# DataAcquisitonBoard.net
KiCad netlist of a schematic drawn in Altium Designer
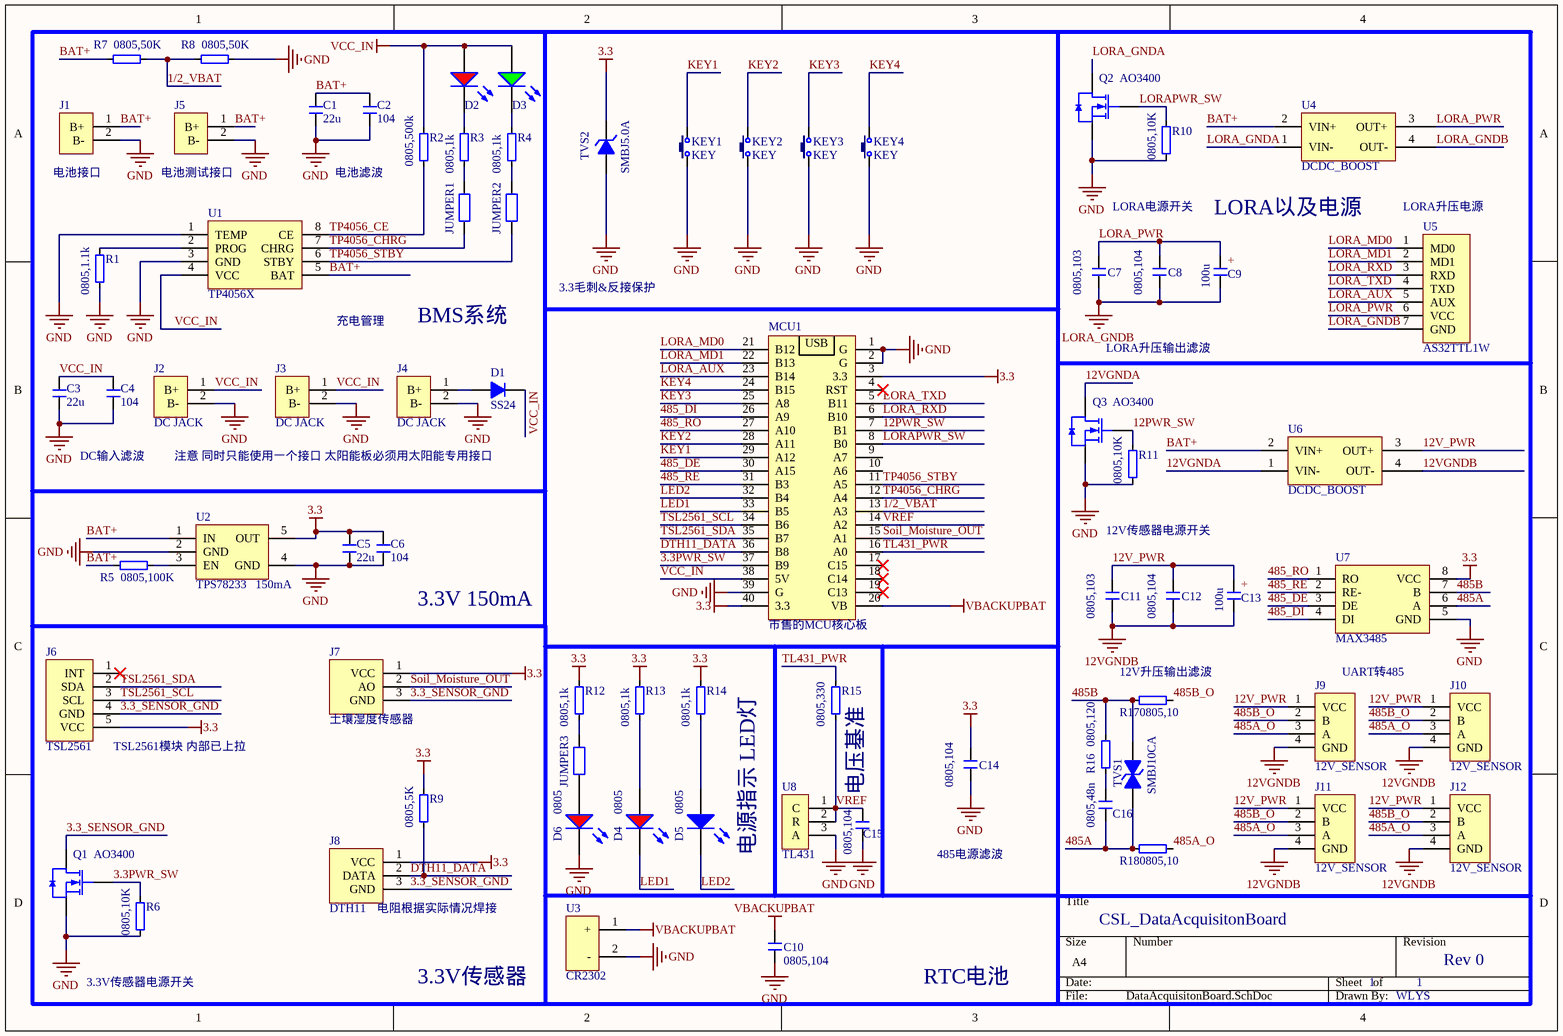
[diagram p0: DataAcquisitonBoard.SchDoc]

(export (version "E")
  (design (tool "Eeschema 10.0.6"))
  (components
    (comp (ref "C1")
      (value "22u")
      (footprint "0805_C")
      (libsource (lib "DataAcquisitonBoard") (part "C0805"))
    )
    (comp (ref "C2")
      (value "104")
      (footprint "0805_C")
      (libsource (lib "DataAcquisitonBoard") (part "C0805"))
    )
    (comp (ref "C3")
      (value "22u")
      (footprint "0805_C")
      (libsource (lib "DataAcquisitonBoard") (part "C0805"))
    )
    (comp (ref "C4")
      (value "104")
      (footprint "0805_C")
      (libsource (lib "DataAcquisitonBoard") (part "C0805"))
    )
    (comp (ref "C5")
      (value "22u")
      (footprint "0805_C")
      (libsource (lib "DataAcquisitonBoard") (part "C0805"))
    )
    (comp (ref "C6")
      (value "104")
      (footprint "0805_C")
      (libsource (lib "DataAcquisitonBoard") (part "C0805"))
    )
    (comp (ref "C7")
      (value "0805,103")
      (footprint "0805_C")
      (libsource (lib "DataAcquisitonBoard") (part "C0805"))
    )
    (comp (ref "C8")
      (value "0805,104")
      (footprint "0805_C")
      (libsource (lib "DataAcquisitonBoard") (part "C0805"))
    )
    (comp (ref "C9")
      (value "100u")
      (footprint "CAP 2.5*6.3*11.2")
      (libsource (lib "DataAcquisitonBoard") (part "C直插电解"))
    )
    (comp (ref "C10")
      (value "0805,104")
      (footprint "0805_C")
      (libsource (lib "DataAcquisitonBoard") (part "C0805"))
    )
    (comp (ref "C11")
      (value "0805,103")
      (footprint "0805_C")
      (libsource (lib "DataAcquisitonBoard") (part "C0805"))
    )
    (comp (ref "C12")
      (value "0805,104")
      (footprint "0805_C")
      (libsource (lib "DataAcquisitonBoard") (part "C0805"))
    )
    (comp (ref "C13")
      (value "100u")
      (footprint "CAP 2.5*6.3*11.2")
      (libsource (lib "DataAcquisitonBoard") (part "C直插电解"))
    )
    (comp (ref "C14")
      (value "0805,104")
      (footprint "0805_C")
      (libsource (lib "DataAcquisitonBoard") (part "C0805"))
    )
    (comp (ref "C15")
      (value "0805,104")
      (footprint "0805_C")
      (libsource (lib "DataAcquisitonBoard") (part "C0805"))
    )
    (comp (ref "C16")
      (value "0805,48n")
      (footprint "0805_C")
      (libsource (lib "DataAcquisitonBoard") (part "C0805"))
    )
    (comp (ref "D1")
      (value "SS24")
      (footprint "SMB(DO-214AA)_S1")
      (description "Diodo diode")
      (libsource (lib "DataAcquisitonBoard") (part "Diodo_214AA"))
    )
    (comp (ref "D2")
      (value "~")
      (footprint "0805_LED_S1")
      (description "发光二极管")
      (libsource (lib "DataAcquisitonBoard") (part "0805 红灯"))
    )
    (comp (ref "D3")
      (value "~")
      (footprint "0805_LED_S1")
      (description "发光二极管")
      (libsource (lib "DataAcquisitonBoard") (part "0805 翠绿"))
    )
    (comp (ref "D4")
      (value "0805")
      (footprint "0805_LED_S1")
      (description "发光二极管")
      (libsource (lib "DataAcquisitonBoard") (part "0805 红灯"))
    )
    (comp (ref "D5")
      (value "0805")
      (footprint "0805_LED_S1")
      (description "发光二极管")
      (libsource (lib "DataAcquisitonBoard") (part "0805 蓝灯"))
    )
    (comp (ref "D6")
      (value "0805")
      (footprint "0805_LED_S1")
      (description "发光二极管")
      (libsource (lib "DataAcquisitonBoard") (part "0805 红灯"))
    )
    (comp (ref "J1")
      (value "电池接口")
      (footprint "XH2.54-LI-2P")
      (libsource (lib "DataAcquisitonBoard") (part "BAT"))
    )
    (comp (ref "J2")
      (value "DC JACK")
      (footprint "XH2.54-LI-2P")
      (description "DC充电输入接口")
      (libsource (lib "DataAcquisitonBoard") (part "DCINPUT"))
    )
    (comp (ref "J3")
      (value "DC JACK")
      (footprint "XH2.54-LI-2P")
      (description "DC充电输入接口")
      (libsource (lib "DataAcquisitonBoard") (part "DCINPUT"))
    )
    (comp (ref "J4")
      (value "DC JACK")
      (footprint "XH2.54-LI-2P")
      (description "DC充电输入接口")
      (libsource (lib "DataAcquisitonBoard") (part "DCINPUT"))
    )
    (comp (ref "J5")
      (value "电池测试接口")
      (footprint "XH2.54-LI-2P")
      (description "电池接口")
      (libsource (lib "DataAcquisitonBoard") (part "BAT"))
    )
    (comp (ref "J6")
      (value "TSL2561")
      (footprint "XH2.54-LI-5P")
      (description "IIC总线光强传感器模块 已经集成IIC上拉电阻")
      (libsource (lib "DataAcquisitonBoard") (part "TSL2561"))
    )
    (comp (ref "J7")
      (value "土壤湿度传感器")
      (footprint "XH2.54-LI-3P")
      (libsource (lib "DataAcquisitonBoard") (part "土壤湿度"))
    )
    (comp (ref "J8")
      (value "DTH11")
      (footprint "XH2.54-LI-3P")
      (description "数字式温湿度传感器")
      (libsource (lib "DataAcquisitonBoard") (part "DTH11"))
    )
    (comp (ref "J9")
      (value "12V_SENSOR")
      (footprint "XH2.54-LI-4P")
      (description "12V传感器接口 包括 12V GND 485")
      (libsource (lib "DataAcquisitonBoard") (part "12V_SENSOR"))
    )
    (comp (ref "J10")
      (value "12V_SENSOR")
      (footprint "XH2.54-LI-4P")
      (description "12V传感器接口 包括 12V GND 485")
      (libsource (lib "DataAcquisitonBoard") (part "12V_SENSOR"))
    )
    (comp (ref "J11")
      (value "12V_SENSOR")
      (footprint "XH2.54-LI-4P")
      (description "12V传感器接口 包括 12V GND 485")
      (libsource (lib "DataAcquisitonBoard") (part "12V_SENSOR"))
    )
    (comp (ref "J12")
      (value "12V_SENSOR")
      (footprint "XH2.54-LI-4P")
      (description "12V传感器接口 包括 12V GND 485")
      (libsource (lib "DataAcquisitonBoard") (part "12V_SENSOR"))
    )
    (comp (ref "JUMPER1")
      (value "0805_JUMPER")
      (footprint "JUMPER")
      (description "0805大小的跳线")
      (libsource (lib "DataAcquisitonBoard") (part "0805_JUMPER"))
    )
    (comp (ref "JUMPER2")
      (value "0805_JUMPER")
      (footprint "JUMPER")
      (description "0805大小的跳线")
      (libsource (lib "DataAcquisitonBoard") (part "0805_JUMPER"))
    )
    (comp (ref "JUMPER3")
      (value "0805_JUMPER")
      (footprint "JUMPER")
      (description "0805大小的跳线")
      (libsource (lib "DataAcquisitonBoard") (part "0805_JUMPER"))
    )
    (comp (ref "KEY1")
      (value "KEY")
      (footprint "TSW SMD-4*4*1.5")
      (description "Tact Switch")
      (libsource (lib "DataAcquisitonBoard") (part "TSW_4x4-SMT"))
    )
    (comp (ref "KEY2")
      (value "KEY")
      (footprint "TSW SMD-4*4*1.5")
      (description "Tact Switch")
      (libsource (lib "DataAcquisitonBoard") (part "TSW_4x4-SMT"))
    )
    (comp (ref "KEY3")
      (value "KEY")
      (footprint "TSW SMD-4*4*1.5")
      (description "Tact Switch")
      (libsource (lib "DataAcquisitonBoard") (part "TSW_4x4-SMT"))
    )
    (comp (ref "KEY4")
      (value "KEY")
      (footprint "TSW SMD-4*4*1.5")
      (description "Tact Switch")
      (libsource (lib "DataAcquisitonBoard") (part "TSW_4x4-SMT"))
    )
    (comp (ref "MCU1")
      (value "市售的MCU核心板")
      (footprint "STM32F103C8T6_CORE")
      (libsource (lib "DataAcquisitonBoard") (part "STM32F103C8T6_CORE"))
    )
    (comp (ref "Q1")
      (value "AO3400")
      (footprint "SOT-23(SOT-23-3)")
      (description "MOS(场效应管)")
      (libsource (lib "DataAcquisitonBoard") (part "AO3400A N道沟 X0YV1T SOT-23"))
    )
    (comp (ref "Q2")
      (value "AO3400")
      (footprint "SOT-23(SOT-23-3)")
      (description "MOS(场效应管)")
      (libsource (lib "DataAcquisitonBoard") (part "AO3400A N道沟 X0YV1T SOT-23"))
    )
    (comp (ref "Q3")
      (value "AO3400")
      (footprint "SOT-23(SOT-23-3)")
      (description "MOS(场效应管)")
      (libsource (lib "DataAcquisitonBoard") (part "AO3400A N道沟 X0YV1T SOT-23"))
    )
    (comp (ref "R1")
      (value "0805,1.1k")
      (footprint "0805_R")
      (libsource (lib "DataAcquisitonBoard") (part "R0805"))
    )
    (comp (ref "R2")
      (value "0805,500k")
      (footprint "0805_R")
      (libsource (lib "DataAcquisitonBoard") (part "R0805"))
    )
    (comp (ref "R3")
      (value "0805,1k")
      (footprint "0805_R")
      (libsource (lib "DataAcquisitonBoard") (part "R0805"))
    )
    (comp (ref "R4")
      (value "0805,1k")
      (footprint "0805_R")
      (libsource (lib "DataAcquisitonBoard") (part "R0805"))
    )
    (comp (ref "R5")
      (value "0805,100K")
      (footprint "0805_R")
      (libsource (lib "DataAcquisitonBoard") (part "R0805"))
    )
    (comp (ref "R6")
      (value "0805,10K")
      (footprint "0805_R")
      (libsource (lib "DataAcquisitonBoard") (part "R0805"))
    )
    (comp (ref "R7")
      (value "0805,50K")
      (footprint "0805_R")
      (libsource (lib "DataAcquisitonBoard") (part "R0805"))
    )
    (comp (ref "R8")
      (value "0805,50K")
      (footprint "0805_R")
      (libsource (lib "DataAcquisitonBoard") (part "R0805"))
    )
    (comp (ref "R9")
      (value "0805,5K")
      (footprint "0805_R")
      (libsource (lib "DataAcquisitonBoard") (part "R0805"))
    )
    (comp (ref "R10")
      (value "0805,10K")
      (footprint "0805_R")
      (libsource (lib "DataAcquisitonBoard") (part "R0805"))
    )
    (comp (ref "R11")
      (value "0805,10K")
      (footprint "0805_R")
      (libsource (lib "DataAcquisitonBoard") (part "R0805"))
    )
    (comp (ref "R12")
      (value "0805,1k")
      (footprint "0805_R")
      (libsource (lib "DataAcquisitonBoard") (part "R0805"))
    )
    (comp (ref "R13")
      (value "0805,1k")
      (footprint "0805_R")
      (libsource (lib "DataAcquisitonBoard") (part "R0805"))
    )
    (comp (ref "R14")
      (value "0805,1k")
      (footprint "0805_R")
      (libsource (lib "DataAcquisitonBoard") (part "R0805"))
    )
    (comp (ref "R15")
      (value "0805,330")
      (footprint "0805_R")
      (libsource (lib "DataAcquisitonBoard") (part "R0805"))
    )
    (comp (ref "R16")
      (value "0805,120")
      (footprint "0805_R")
      (libsource (lib "DataAcquisitonBoard") (part "R0805"))
    )
    (comp (ref "R17")
      (value "0805,10")
      (footprint "0805_R")
      (libsource (lib "DataAcquisitonBoard") (part "R0805"))
    )
    (comp (ref "R18")
      (value "0805,10")
      (footprint "0805_R")
      (libsource (lib "DataAcquisitonBoard") (part "R0805"))
    )
    (comp (ref "TVS1")
      (value "SMBJ10CA")
      (footprint "SMB(DO-214AA)_S1")
      (description "双向TVS 214AA封装")
      (libsource (lib "DataAcquisitonBoard") (part "TVS_214AA_BI"))
    )
    (comp (ref "TVS2")
      (value "SMBJ5.0A")
      (footprint "SMB(DO-214AA)_S1")
      (description "TVS diode")
      (libsource (lib "DataAcquisitonBoard") (part "TVS_214AA"))
    )
    (comp (ref "U1")
      (value "TP4056X")
      (footprint "SOIC-8_150mil")
      (description "防反接锂电池充电管理IC")
      (libsource (lib "DataAcquisitonBoard") (part "TP4056X"))
    )
    (comp (ref "U2")
      (value "TPS78233")
      (footprint "SOT-23-5")
      (description "Regulator_SMT")
      (fields (field (name "版权归属") "源创客"))
      (libsource (lib "DataAcquisitonBoard") (part "TPS782"))
    )
    (comp (ref "U3")
      (value "CR2302")
      (footprint "CR2032_A")
      (description "CR2302 3V电池")
      (libsource (lib "DataAcquisitonBoard") (part "CR2302"))
    )
    (comp (ref "U4")
      (value "DCDC_BOOST")
      (footprint "BOOSTER")
      (libsource (lib "DataAcquisitonBoard") (part "DCDC_BOOST"))
    )
    (comp (ref "U5")
      (value "AS32TTL1W")
      (footprint "LORA")
      (description "1W LORA无线串口")
      (libsource (lib "DataAcquisitonBoard") (part "LORA_AS32TTL1W"))
    )
    (comp (ref "U6")
      (value "DCDC_BOOST")
      (footprint "BOOSTER")
      (libsource (lib "DataAcquisitonBoard") (part "DCDC_BOOST"))
    )
    (comp (ref "U7")
      (value "MAX3485")
      (footprint "SOIC-8_150mil")
      (description "3.3V供电带关断485半双工收发器")
      (libsource (lib "DataAcquisitonBoard") (part "MAX3485"))
    )
    (comp (ref "U8")
      (value "TL431")
      (footprint "SOT-23(SOT-23-3)")
      (description "德州仪器TL431 非国产TL431")
      (libsource (lib "DataAcquisitonBoard") (part "TL431AIDBZR"))
    )
  )
  (nets
    (net (code "1") (name "/1{slash}2_VBAT") (class "Default")
      (node (ref "MCU1") (pin "13") (pinfunction "A3_13") (pintype "passive"))
      (node (ref "R7") (pin "1") (pinfunction "1_1") (pintype "passive"))
      (node (ref "R8") (pin "2") (pinfunction "2_2") (pintype "passive"))
    )
    (net (code "2") (name "/3.3PWR_SW") (class "Default")
      (node (ref "MCU1") (pin "37") (pinfunction "B9_37") (pintype "passive"))
      (node (ref "Q1") (pin "1") (pinfunction "G_1") (pintype "passive"))
      (node (ref "R6") (pin "1") (pinfunction "1_1") (pintype "passive"))
    )
    (net (code "3") (name "/3.3_SENSOR_GND") (class "Default")
      (node (ref "J6") (pin "4") (pinfunction "GND_4") (pintype "passive"))
      (node (ref "J7") (pin "3") (pinfunction "GND_3") (pintype "passive"))
      (node (ref "J8") (pin "3") (pinfunction "GND_3") (pintype "passive"))
      (node (ref "Q1") (pin "3") (pinfunction "D_3") (pintype "passive"))
    )
    (net (code "4") (name "/12PWR_SW") (class "Default")
      (node (ref "MCU1") (pin "7") (pinfunction "B1_7") (pintype "passive"))
      (node (ref "Q3") (pin "1") (pinfunction "G_1") (pintype "passive"))
      (node (ref "R11") (pin "1") (pinfunction "1_1") (pintype "passive"))
    )
    (net (code "5") (name "/12VGNDA") (class "Default")
      (node (ref "Q3") (pin "3") (pinfunction "D_3") (pintype "passive"))
      (node (ref "U6") (pin "1") (pinfunction "VIN-_1") (pintype "passive"))
    )
    (net (code "6") (name "/12V_PWR") (class "Default")
      (node (ref "C11") (pin "1") (pinfunction "1_1") (pintype "passive"))
      (node (ref "C12") (pin "1") (pinfunction "1_1") (pintype "passive"))
      (node (ref "C13") (pin "1") (pinfunction "1_1") (pintype "passive"))
      (node (ref "J10") (pin "1") (pinfunction "VCC_1") (pintype "passive"))
      (node (ref "J11") (pin "1") (pinfunction "VCC_1") (pintype "passive"))
      (node (ref "J12") (pin "1") (pinfunction "VCC_1") (pintype "passive"))
      (node (ref "J9") (pin "1") (pinfunction "VCC_1") (pintype "passive"))
      (node (ref "U6") (pin "3") (pinfunction "OUT+_3") (pintype "passive"))
    )
    (net (code "7") (name "/485A") (class "Default")
      (node (ref "C16") (pin "2") (pinfunction "2_2") (pintype "passive"))
      (node (ref "R18") (pin "2") (pinfunction "2_2") (pintype "passive"))
      (node (ref "TVS1") (pin "1") (pinfunction "A_1") (pintype "passive"))
      (node (ref "U7") (pin "6") (pinfunction "A_6") (pintype "passive"))
    )
    (net (code "8") (name "/485A_O") (class "Default")
      (node (ref "J10") (pin "3") (pinfunction "A_3") (pintype "passive"))
      (node (ref "J11") (pin "3") (pinfunction "A_3") (pintype "passive"))
      (node (ref "J12") (pin "3") (pinfunction "A_3") (pintype "passive"))
      (node (ref "J9") (pin "3") (pinfunction "A_3") (pintype "passive"))
      (node (ref "R18") (pin "1") (pinfunction "1_1") (pintype "passive"))
    )
    (net (code "9") (name "/485B") (class "Default")
      (node (ref "R16") (pin "1") (pinfunction "1_1") (pintype "passive"))
      (node (ref "R17") (pin "2") (pinfunction "2_2") (pintype "passive"))
      (node (ref "TVS1") (pin "2") (pinfunction "K_2") (pintype "passive"))
      (node (ref "U7") (pin "7") (pinfunction "B_7") (pintype "passive"))
    )
    (net (code "10") (name "/485B_O") (class "Default")
      (node (ref "J10") (pin "2") (pinfunction "B_2") (pintype "passive"))
      (node (ref "J11") (pin "2") (pinfunction "B_2") (pintype "passive"))
      (node (ref "J12") (pin "2") (pinfunction "B_2") (pintype "passive"))
      (node (ref "J9") (pin "2") (pinfunction "B_2") (pintype "passive"))
      (node (ref "R17") (pin "1") (pinfunction "1_1") (pintype "passive"))
    )
    (net (code "11") (name "/485_DE") (class "Default")
      (node (ref "MCU1") (pin "30") (pinfunction "A15_30") (pintype "passive"))
      (node (ref "U7") (pin "3") (pinfunction "DE_3") (pintype "passive"))
    )
    (net (code "12") (name "/485_DI") (class "Default")
      (node (ref "MCU1") (pin "26") (pinfunction "A9_26") (pintype "passive"))
      (node (ref "U7") (pin "4") (pinfunction "DI_4") (pintype "passive"))
    )
    (net (code "13") (name "/485_RE") (class "Default")
      (node (ref "MCU1") (pin "31") (pinfunction "B3_31") (pintype "passive"))
      (node (ref "U7") (pin "2") (pinfunction "RE-_2") (pintype "passive"))
    )
    (net (code "14") (name "/485_RO") (class "Default")
      (node (ref "MCU1") (pin "27") (pinfunction "A10_27") (pintype "passive"))
      (node (ref "U7") (pin "1") (pinfunction "RO_1") (pintype "passive"))
    )
    (net (code "15") (name "/BAT+") (class "Default")
      (node (ref "C1") (pin "1") (pinfunction "1_1") (pintype "passive"))
      (node (ref "C2") (pin "1") (pinfunction "1_1") (pintype "passive"))
      (node (ref "J1") (pin "1") (pinfunction "B+_1") (pintype "passive"))
      (node (ref "J5") (pin "1") (pinfunction "B+_1") (pintype "passive"))
      (node (ref "R5") (pin "2") (pinfunction "2_2") (pintype "passive"))
      (node (ref "R7") (pin "2") (pinfunction "2_2") (pintype "passive"))
      (node (ref "U1") (pin "5") (pinfunction "BAT_5") (pintype "passive"))
      (node (ref "U2") (pin "1") (pinfunction "IN_1") (pintype "passive"))
      (node (ref "U4") (pin "2") (pinfunction "VIN+_2") (pintype "passive"))
      (node (ref "U6") (pin "2") (pinfunction "VIN+_2") (pintype "passive"))
    )
    (net (code "16") (name "/DTH11_DATA") (class "Default")
      (node (ref "J8") (pin "2") (pinfunction "DATA_2") (pintype "passive"))
      (node (ref "MCU1") (pin "36") (pinfunction "B8_36") (pintype "passive"))
      (node (ref "R9") (pin "2") (pinfunction "2_2") (pintype "passive"))
    )
    (net (code "17") (name "/KEY1") (class "Default")
      (node (ref "KEY1") (pin "2") (pinfunction "2_2") (pintype "passive"))
      (node (ref "MCU1") (pin "29") (pinfunction "A12_29") (pintype "passive"))
    )
    (net (code "18") (name "/KEY2") (class "Default")
      (node (ref "KEY2") (pin "2") (pinfunction "2_2") (pintype "passive"))
      (node (ref "MCU1") (pin "28") (pinfunction "A11_28") (pintype "passive"))
    )
    (net (code "19") (name "/KEY3") (class "Default")
      (node (ref "KEY3") (pin "2") (pinfunction "2_2") (pintype "passive"))
      (node (ref "MCU1") (pin "25") (pinfunction "A8_25") (pintype "passive"))
    )
    (net (code "20") (name "/KEY4") (class "Default")
      (node (ref "KEY4") (pin "2") (pinfunction "2_2") (pintype "passive"))
      (node (ref "MCU1") (pin "24") (pinfunction "B15_24") (pintype "passive"))
    )
    (net (code "21") (name "/LED1") (class "Default")
      (node (ref "D4") (pin "K") (pinfunction "K_K") (pintype "passive"))
      (node (ref "MCU1") (pin "33") (pinfunction "B5_33") (pintype "passive"))
    )
    (net (code "22") (name "/LED2") (class "Default")
      (node (ref "D5") (pin "K") (pinfunction "K_K") (pintype "passive"))
      (node (ref "MCU1") (pin "32") (pinfunction "B4_32") (pintype "passive"))
    )
    (net (code "23") (name "/LORAPWR_SW") (class "Default")
      (node (ref "MCU1") (pin "8") (pinfunction "B0_8") (pintype "passive"))
      (node (ref "Q2") (pin "1") (pinfunction "G_1") (pintype "passive"))
      (node (ref "R10") (pin "1") (pinfunction "1_1") (pintype "passive"))
    )
    (net (code "24") (name "/LORA_AUX") (class "Default")
      (node (ref "MCU1") (pin "23") (pinfunction "B14_23") (pintype "passive"))
      (node (ref "U5") (pin "5") (pinfunction "AUX_5") (pintype "passive"))
    )
    (net (code "25") (name "/LORA_GNDA") (class "Default")
      (node (ref "Q2") (pin "3") (pinfunction "D_3") (pintype "passive"))
      (node (ref "U4") (pin "1") (pinfunction "VIN-_1") (pintype "passive"))
    )
    (net (code "26") (name "/LORA_MD0") (class "Default")
      (node (ref "MCU1") (pin "21") (pinfunction "B12_21") (pintype "passive"))
      (node (ref "U5") (pin "1") (pinfunction "MD0_1") (pintype "passive"))
    )
    (net (code "27") (name "/LORA_MD1") (class "Default")
      (node (ref "MCU1") (pin "22") (pinfunction "B13_22") (pintype "passive"))
      (node (ref "U5") (pin "2") (pinfunction "MD1_2") (pintype "passive"))
    )
    (net (code "28") (name "/LORA_PWR") (class "Default")
      (node (ref "C7") (pin "1") (pinfunction "1_1") (pintype "passive"))
      (node (ref "C8") (pin "1") (pinfunction "1_1") (pintype "passive"))
      (node (ref "C9") (pin "1") (pinfunction "1_1") (pintype "passive"))
      (node (ref "U4") (pin "3") (pinfunction "OUT+_3") (pintype "passive"))
      (node (ref "U5") (pin "6") (pinfunction "VCC_6") (pintype "passive"))
    )
    (net (code "29") (name "/LORA_RXD") (class "Default")
      (node (ref "MCU1") (pin "6") (pinfunction "B10_6") (pintype "passive"))
      (node (ref "U5") (pin "3") (pinfunction "RXD_3") (pintype "passive"))
    )
    (net (code "30") (name "/LORA_TXD") (class "Default")
      (node (ref "MCU1") (pin "5") (pinfunction "B11_5") (pintype "passive"))
      (node (ref "U5") (pin "4") (pinfunction "TXD_4") (pintype "passive"))
    )
    (net (code "31") (name "/Soil_Moisture_OUT") (class "Default")
      (node (ref "J7") (pin "2") (pinfunction "AO_2") (pintype "passive"))
      (node (ref "MCU1") (pin "15") (pinfunction "A1_15") (pintype "passive"))
    )
    (net (code "32") (name "/TL431_PWR") (class "Default")
      (node (ref "MCU1") (pin "16") (pinfunction "A0_16") (pintype "passive"))
      (node (ref "R15") (pin "2") (pinfunction "2_2") (pintype "passive"))
    )
    (net (code "33") (name "/TP4056_CE") (class "Default")
      (node (ref "R2") (pin "1") (pinfunction "1_1") (pintype "passive"))
      (node (ref "U1") (pin "8") (pinfunction "CE_8") (pintype "passive"))
    )
    (net (code "34") (name "/TP4056_CHRG") (class "Default")
      (node (ref "JUMPER1") (pin "1") (pinfunction "1_1") (pintype "passive"))
      (node (ref "MCU1") (pin "12") (pinfunction "A4_12") (pintype "passive"))
      (node (ref "U1") (pin "7") (pinfunction "CHRG_7") (pintype "passive"))
    )
    (net (code "35") (name "/TP4056_STBY") (class "Default")
      (node (ref "JUMPER2") (pin "1") (pinfunction "1_1") (pintype "passive"))
      (node (ref "MCU1") (pin "11") (pinfunction "A5_11") (pintype "passive"))
      (node (ref "U1") (pin "6") (pinfunction "STBY_6") (pintype "passive"))
    )
    (net (code "36") (name "/TSL2561_SCL") (class "Default")
      (node (ref "J6") (pin "3") (pinfunction "SCL_3") (pintype "passive"))
      (node (ref "MCU1") (pin "34") (pinfunction "B6_34") (pintype "passive"))
    )
    (net (code "37") (name "/TSL2561_SDA") (class "Default")
      (node (ref "J6") (pin "2") (pinfunction "SDA_2") (pintype "passive"))
      (node (ref "MCU1") (pin "35") (pinfunction "B7_35") (pintype "passive"))
    )
    (net (code "38") (name "/VREF") (class "Default")
      (node (ref "C15") (pin "1") (pinfunction "1_1") (pintype "passive"))
      (node (ref "MCU1") (pin "14") (pinfunction "A2_14") (pintype "passive"))
      (node (ref "R15") (pin "1") (pinfunction "1_1") (pintype "passive"))
      (node (ref "U8") (pin "1") (pinfunction "C_1") (pintype "passive"))
      (node (ref "U8") (pin "2") (pinfunction "R_2") (pintype "passive"))
    )
    (net (code "39") (name "3.3") (class "Default")
      (node (ref "C14") (pin "1") (pinfunction "1_1") (pintype "passive"))
      (node (ref "C5") (pin "1") (pinfunction "1_1") (pintype "passive"))
      (node (ref "C6") (pin "1") (pinfunction "1_1") (pintype "passive"))
      (node (ref "J6") (pin "5") (pinfunction "VCC_5") (pintype "passive"))
      (node (ref "J7") (pin "1") (pinfunction "VCC_1") (pintype "passive"))
      (node (ref "J8") (pin "1") (pinfunction "VCC_1") (pintype "passive"))
      (node (ref "MCU1") (pin "3") (pinfunction "3.3_3") (pintype "passive"))
      (node (ref "MCU1") (pin "40") (pinfunction "3.3_40") (pintype "passive"))
      (node (ref "R12") (pin "2") (pinfunction "2_2") (pintype "passive"))
      (node (ref "R13") (pin "2") (pinfunction "2_2") (pintype "passive"))
      (node (ref "R14") (pin "2") (pinfunction "2_2") (pintype "passive"))
      (node (ref "R9") (pin "1") (pinfunction "1_1") (pintype "passive"))
      (node (ref "TVS2") (pin "2") (pinfunction "K_2") (pintype "passive"))
      (node (ref "U2") (pin "5") (pinfunction "OUT_5") (pintype "passive"))
      (node (ref "U7") (pin "8") (pinfunction "VCC_8") (pintype "passive"))
    )
    (net (code "40") (name "12VGNDB") (class "Default")
      (node (ref "C11") (pin "2") (pinfunction "2_2") (pintype "passive"))
      (node (ref "C12") (pin "2") (pinfunction "2_2") (pintype "passive"))
      (node (ref "C13") (pin "2") (pinfunction "2_2") (pintype "passive"))
      (node (ref "J10") (pin "4") (pinfunction "GND_4") (pintype "passive"))
      (node (ref "J11") (pin "4") (pinfunction "GND_4") (pintype "passive"))
      (node (ref "J12") (pin "4") (pinfunction "GND_4") (pintype "passive"))
      (node (ref "J9") (pin "4") (pinfunction "GND_4") (pintype "passive"))
      (node (ref "U6") (pin "4") (pinfunction "OUT-_4") (pintype "passive"))
    )
    (net (code "41") (name "GND") (class "Default")
      (node (ref "C1") (pin "2") (pinfunction "2_2") (pintype "passive"))
      (node (ref "C10") (pin "2") (pinfunction "2_2") (pintype "passive"))
      (node (ref "C14") (pin "2") (pinfunction "2_2") (pintype "passive"))
      (node (ref "C15") (pin "2") (pinfunction "2_2") (pintype "passive"))
      (node (ref "C2") (pin "2") (pinfunction "2_2") (pintype "passive"))
      (node (ref "C3") (pin "2") (pinfunction "2_2") (pintype "passive"))
      (node (ref "C4") (pin "2") (pinfunction "2_2") (pintype "passive"))
      (node (ref "C5") (pin "2") (pinfunction "2_2") (pintype "passive"))
      (node (ref "C6") (pin "2") (pinfunction "2_2") (pintype "passive"))
      (node (ref "D6") (pin "K") (pinfunction "K_K") (pintype "passive"))
      (node (ref "J1") (pin "2") (pinfunction "B-_2") (pintype "passive"))
      (node (ref "J2") (pin "2") (pinfunction "B-_2") (pintype "passive"))
      (node (ref "J3") (pin "2") (pinfunction "B-_2") (pintype "passive"))
      (node (ref "J4") (pin "2") (pinfunction "B-_2") (pintype "passive"))
      (node (ref "J5") (pin "2") (pinfunction "B-_2") (pintype "passive"))
      (node (ref "KEY1") (pin "1") (pinfunction "1_1") (pintype "passive"))
      (node (ref "KEY2") (pin "1") (pinfunction "1_1") (pintype "passive"))
      (node (ref "KEY3") (pin "1") (pinfunction "1_1") (pintype "passive"))
      (node (ref "KEY4") (pin "1") (pinfunction "1_1") (pintype "passive"))
      (node (ref "MCU1") (pin "1") (pinfunction "G_1") (pintype "passive"))
      (node (ref "MCU1") (pin "2") (pinfunction "G_2") (pintype "passive"))
      (node (ref "MCU1") (pin "39") (pinfunction "G_39") (pintype "passive"))
      (node (ref "Q1") (pin "2") (pinfunction "S_2") (pintype "passive"))
      (node (ref "Q2") (pin "2") (pinfunction "S_2") (pintype "passive"))
      (node (ref "Q3") (pin "2") (pinfunction "S_2") (pintype "passive"))
      (node (ref "R1") (pin "1") (pinfunction "1_1") (pintype "passive"))
      (node (ref "R10") (pin "2") (pinfunction "2_2") (pintype "passive"))
      (node (ref "R11") (pin "2") (pinfunction "2_2") (pintype "passive"))
      (node (ref "R6") (pin "2") (pinfunction "2_2") (pintype "passive"))
      (node (ref "R8") (pin "1") (pinfunction "1_1") (pintype "passive"))
      (node (ref "TVS2") (pin "1") (pinfunction "A_1") (pintype "passive"))
      (node (ref "U1") (pin "1") (pinfunction "TEMP_1") (pintype "passive"))
      (node (ref "U1") (pin "3") (pinfunction "GND_3") (pintype "passive"))
      (node (ref "U2") (pin "2") (pinfunction "GND_2") (pintype "passive"))
      (node (ref "U2") (pin "4") (pinfunction "GND_4") (pintype "passive"))
      (node (ref "U3") (pin "2") (pinfunction "-_2") (pintype "passive"))
      (node (ref "U7") (pin "5") (pinfunction "GND_5") (pintype "passive"))
      (node (ref "U8") (pin "3") (pinfunction "A_3") (pintype "passive"))
    )
    (net (code "42") (name "LORA_GNDB") (class "Default")
      (node (ref "C7") (pin "2") (pinfunction "2_2") (pintype "passive"))
      (node (ref "C8") (pin "2") (pinfunction "2_2") (pintype "passive"))
      (node (ref "C9") (pin "2") (pinfunction "2_2") (pintype "passive"))
      (node (ref "U4") (pin "4") (pinfunction "OUT-_4") (pintype "passive"))
      (node (ref "U5") (pin "7") (pinfunction "GND_7") (pintype "passive"))
    )
    (net (code "43") (name "Net-(C16-Pad1)") (class "Default")
      (node (ref "C16") (pin "1") (pinfunction "1_1") (pintype "passive"))
      (node (ref "R16") (pin "2") (pinfunction "2_2") (pintype "passive"))
    )
    (net (code "44") (name "Net-(D1-A)") (class "Default")
      (node (ref "D1") (pin "1") (pinfunction "A_1") (pintype "passive"))
      (node (ref "J4") (pin "1") (pinfunction "B+_1") (pintype "passive"))
    )
    (net (code "45") (name "Net-(D2-PadK)") (class "Default")
      (node (ref "D2") (pin "K") (pinfunction "K_K") (pintype "passive"))
      (node (ref "R3") (pin "2") (pinfunction "2_2") (pintype "passive"))
    )
    (net (code "46") (name "Net-(D3-PadK)") (class "Default")
      (node (ref "D3") (pin "K") (pinfunction "K_K") (pintype "passive"))
      (node (ref "R4") (pin "2") (pinfunction "2_2") (pintype "passive"))
    )
    (net (code "47") (name "Net-(D4-PadA)") (class "Default")
      (node (ref "D4") (pin "A") (pinfunction "A_A") (pintype "passive"))
      (node (ref "R13") (pin "1") (pinfunction "1_1") (pintype "passive"))
    )
    (net (code "48") (name "Net-(D5-PadA)") (class "Default")
      (node (ref "D5") (pin "A") (pinfunction "A_A") (pintype "passive"))
      (node (ref "R14") (pin "1") (pinfunction "1_1") (pintype "passive"))
    )
    (net (code "49") (name "Net-(D6-PadA)") (class "Default")
      (node (ref "D6") (pin "A") (pinfunction "A_A") (pintype "passive"))
      (node (ref "JUMPER3") (pin "1") (pinfunction "1_1") (pintype "passive"))
    )
    (net (code "50") (name "Net-(JUMPER1-Pad2)") (class "Default")
      (node (ref "JUMPER1") (pin "2") (pinfunction "2_2") (pintype "passive"))
      (node (ref "R3") (pin "1") (pinfunction "1_1") (pintype "passive"))
    )
    (net (code "51") (name "Net-(JUMPER2-Pad2)") (class "Default")
      (node (ref "JUMPER2") (pin "2") (pinfunction "2_2") (pintype "passive"))
      (node (ref "R4") (pin "1") (pinfunction "1_1") (pintype "passive"))
    )
    (net (code "52") (name "Net-(JUMPER3-Pad2)") (class "Default")
      (node (ref "JUMPER3") (pin "2") (pinfunction "2_2") (pintype "passive"))
      (node (ref "R12") (pin "1") (pinfunction "1_1") (pintype "passive"))
    )
    (net (code "53") (name "Net-(U1-PROG)") (class "Default")
      (node (ref "R1") (pin "2") (pinfunction "2_2") (pintype "passive"))
      (node (ref "U1") (pin "2") (pinfunction "PROG_2") (pintype "passive"))
    )
    (net (code "54") (name "Net-(U2-EN)") (class "Default")
      (node (ref "R5") (pin "1") (pinfunction "1_1") (pintype "passive"))
      (node (ref "U2") (pin "3") (pinfunction "EN_3") (pintype "passive"))
    )
    (net (code "55") (name "VBACKUPBAT") (class "Default")
      (node (ref "C10") (pin "1") (pinfunction "1_1") (pintype "passive"))
      (node (ref "MCU1") (pin "20") (pinfunction "VB_20") (pintype "passive"))
      (node (ref "U3") (pin "1") (pinfunction "+_1") (pintype "passive"))
    )
    (net (code "56") (name "VCC_IN") (class "Default")
      (node (ref "C3") (pin "1") (pinfunction "1_1") (pintype "passive"))
      (node (ref "C4") (pin "1") (pinfunction "1_1") (pintype "passive"))
      (node (ref "D1") (pin "2") (pinfunction "K_2") (pintype "passive"))
      (node (ref "D2") (pin "A") (pinfunction "A_A") (pintype "passive"))
      (node (ref "D3") (pin "A") (pinfunction "A_A") (pintype "passive"))
      (node (ref "J2") (pin "1") (pinfunction "B+_1") (pintype "passive"))
      (node (ref "J3") (pin "1") (pinfunction "B+_1") (pintype "passive"))
      (node (ref "MCU1") (pin "38") (pinfunction "5V_38") (pintype "passive"))
      (node (ref "R2") (pin "2") (pinfunction "2_2") (pintype "passive"))
      (node (ref "U1") (pin "4") (pinfunction "VCC_4") (pintype "passive"))
    )
    (net (code "57") (name "unconnected-(J6-INT-Pad1)") (class "Default")
      (node (ref "J6") (pin "1") (pinfunction "INT_1") (pintype "passive+no_connect"))
    )
    (net (code "58") (name "unconnected-(MCU1-A6-Pad10)") (class "Default")
      (node (ref "MCU1") (pin "10") (pinfunction "A6_10") (pintype "passive"))
    )
    (net (code "59") (name "unconnected-(MCU1-A7-Pad9)") (class "Default")
      (node (ref "MCU1") (pin "9") (pinfunction "A7_9") (pintype "passive"))
    )
    (net (code "60") (name "unconnected-(MCU1-C13-Pad19)") (class "Default")
      (node (ref "MCU1") (pin "19") (pinfunction "C13_19") (pintype "passive+no_connect"))
    )
    (net (code "61") (name "unconnected-(MCU1-C14-Pad18)") (class "Default")
      (node (ref "MCU1") (pin "18") (pinfunction "C14_18") (pintype "passive+no_connect"))
    )
    (net (code "62") (name "unconnected-(MCU1-C15-Pad17)") (class "Default")
      (node (ref "MCU1") (pin "17") (pinfunction "C15_17") (pintype "passive+no_connect"))
    )
    (net (code "63") (name "unconnected-(MCU1-RST-Pad4)") (class "Default")
      (node (ref "MCU1") (pin "4") (pinfunction "RST_4") (pintype "passive+no_connect"))
    )
  )
)
